# Order339499-SandyNoble-Polarshield_v1_4a.net
KiCad netlist of a schematic drawn in EAGLE
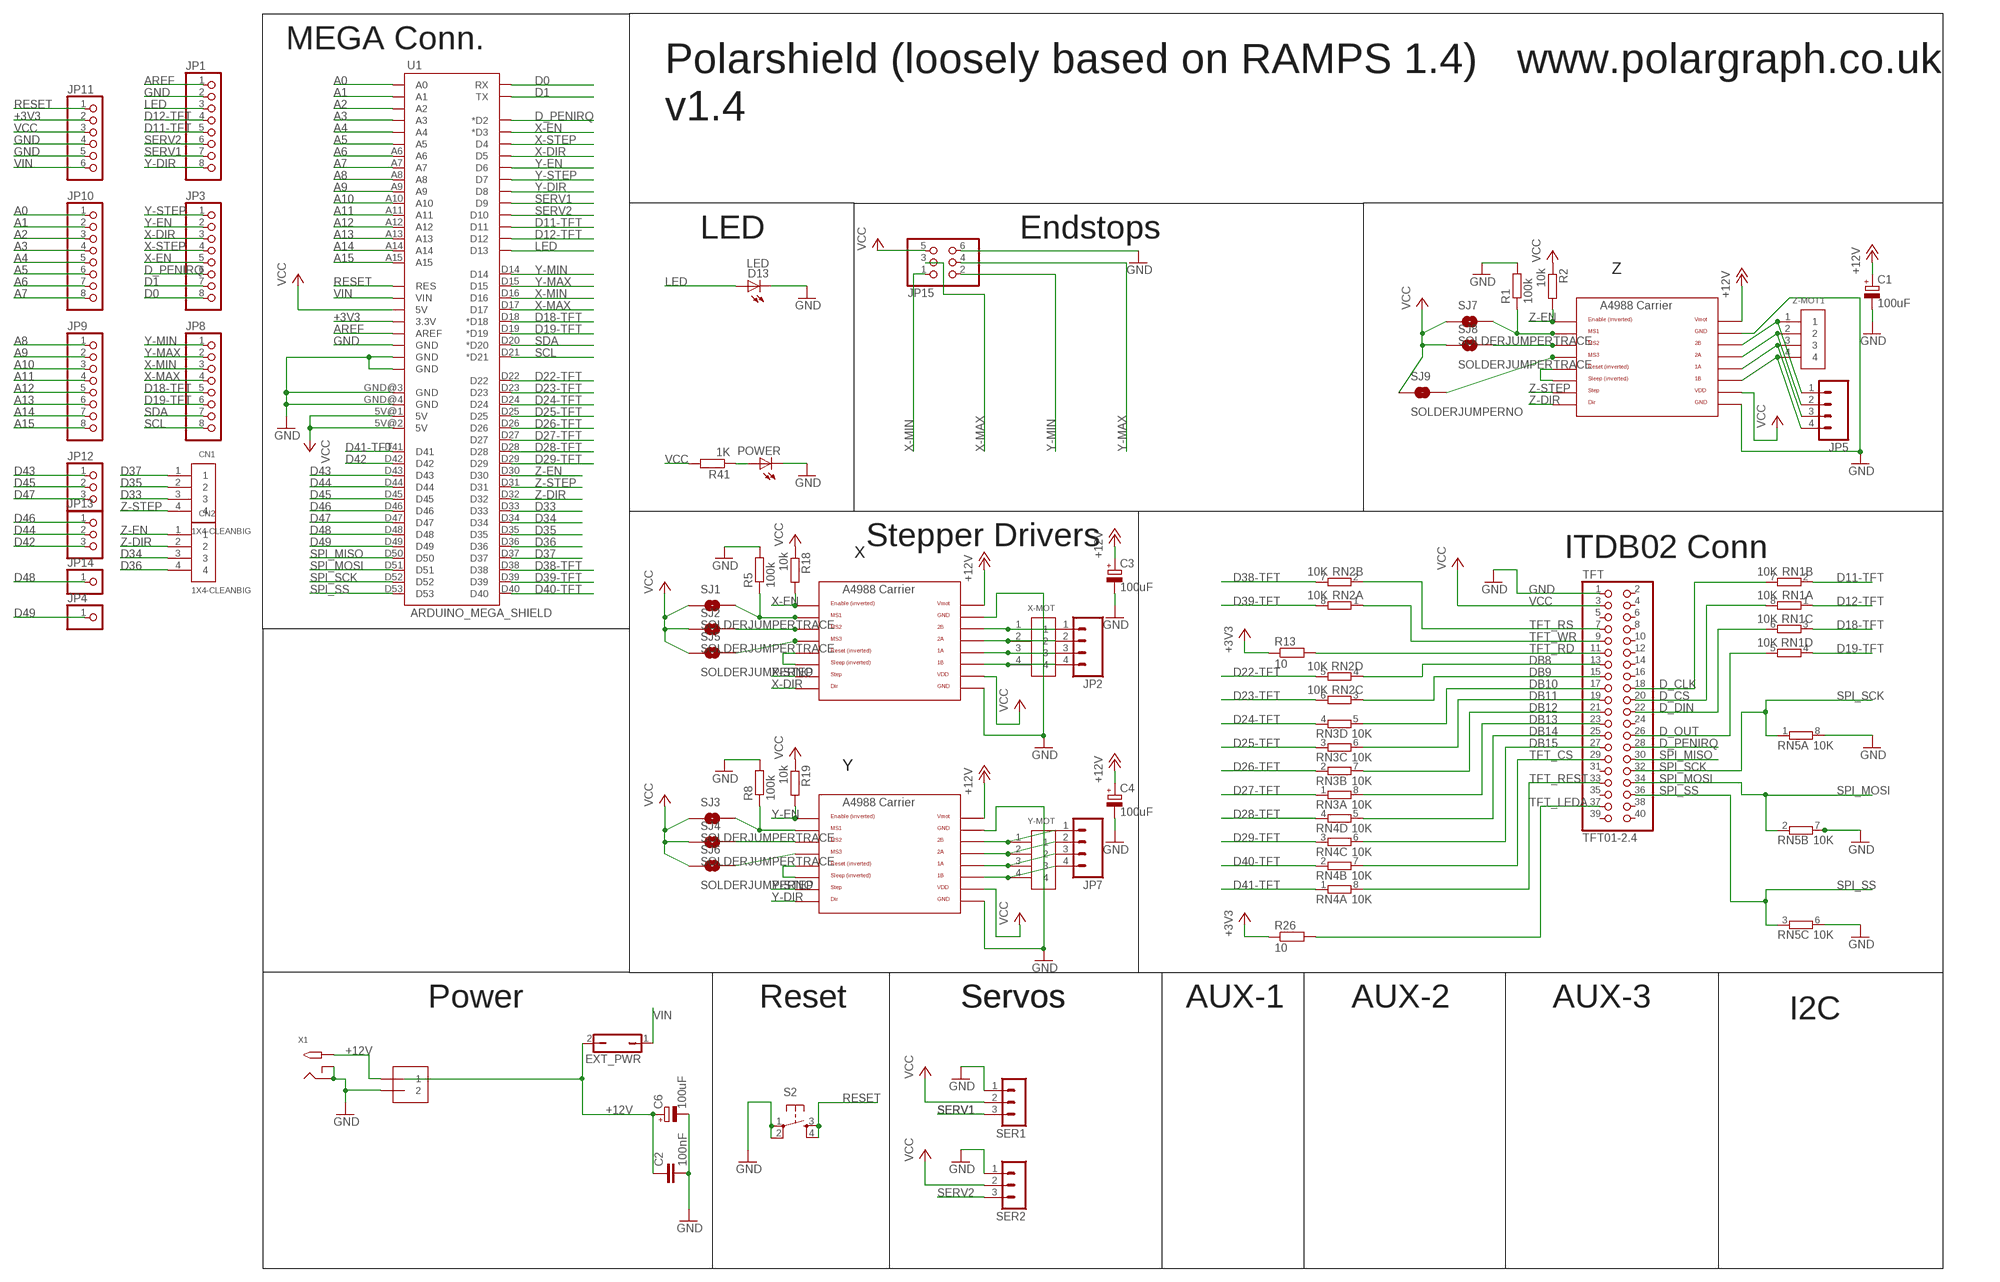
[diagram p0: schematic, sheet 1]

(export (version "E")
  (design (tool "Eeschema 10.0.6"))
  (components
    (comp (ref "C1")
      (value "100uF")
      (footprint "eagle-import:153CLV-0605")
      (libsource (lib "eagle-import") (part "CPOL-EU153CLV-0605"))
    )
    (comp (ref "C2")
      (value "100nF")
      (footprint "eagle-import:C0805")
      (libsource (lib "eagle-import") (part "C-EUC0805"))
    )
    (comp (ref "C3")
      (value "100uF")
      (footprint "eagle-import:153CLV-0605")
      (libsource (lib "eagle-import") (part "CPOL-EU153CLV-0605"))
    )
    (comp (ref "C4")
      (value "100uF")
      (footprint "eagle-import:153CLV-0605")
      (libsource (lib "eagle-import") (part "CPOL-EU153CLV-0605"))
    )
    (comp (ref "C6")
      (value "100uF")
      (footprint "eagle-import:153CLV-0605")
      (libsource (lib "eagle-import") (part "CPOL-EU153CLV-0605"))
    )
    (comp (ref "CN1")
      (value "1X4-CLEANBIG")
      (footprint "eagle-import:1X04-CLEANBIG")
      (libsource (lib "eagle-import") (part "1X4-CLEANBIG"))
    )
    (comp (ref "CN2")
      (value "1X4-CLEANBIG")
      (footprint "eagle-import:1X04-CLEANBIG")
      (libsource (lib "eagle-import") (part "1X4-CLEANBIG"))
    )
    (comp (ref "D13")
      (value "LED")
      (footprint "eagle-import:CHIP-LED0805")
      (libsource (lib "eagle-import") (part "LEDCHIP-LED0805"))
    )
    (comp (ref "EXT_PWR")
      (value "JP1Q")
      (footprint "eagle-import:JP1")
      (libsource (lib "eagle-import") (part "JP1Q"))
    )
    (comp (ref "J1")
      (value "1X2-3.5MM")
      (footprint "eagle-import:1X2-3.5MM")
      (libsource (lib "eagle-import") (part "1X2-3.5MM"))
    )
    (comp (ref "JP1")
      (value "PINHD-1X8CLEANBIG")
      (footprint "eagle-import:1X08-CLEANBIG")
      (libsource (lib "eagle-import") (part "PINHD-1X8CLEANBIG"))
    )
    (comp (ref "JP2")
      (value "M04SCREW")
      (footprint "eagle-import:SCREWTERMINAL-3.5MM-4")
      (libsource (lib "eagle-import") (part "M04SCREW"))
    )
    (comp (ref "JP3")
      (value "PINHD-1X8CLEANBIG")
      (footprint "eagle-import:1X08-CLEANBIG")
      (libsource (lib "eagle-import") (part "PINHD-1X8CLEANBIG"))
    )
    (comp (ref "JP4")
      (value "PINHD-1X1CB")
      (footprint "eagle-import:1X01-CLEANBIG")
      (libsource (lib "eagle-import") (part "PINHD-1X1CB"))
    )
    (comp (ref "JP5")
      (value "M04SCREW")
      (footprint "eagle-import:SCREWTERMINAL-3.5MM-4")
      (libsource (lib "eagle-import") (part "M04SCREW"))
    )
    (comp (ref "JP7")
      (value "M04SCREW")
      (footprint "eagle-import:SCREWTERMINAL-3.5MM-4")
      (libsource (lib "eagle-import") (part "M04SCREW"))
    )
    (comp (ref "JP8")
      (value "PINHD-1X8CLEANBIG")
      (footprint "eagle-import:1X08-CLEANBIG")
      (libsource (lib "eagle-import") (part "PINHD-1X8CLEANBIG"))
    )
    (comp (ref "JP9")
      (value "PINHD-1X8CLEANBIG")
      (footprint "eagle-import:1X08-CLEANBIG")
      (libsource (lib "eagle-import") (part "PINHD-1X8CLEANBIG"))
    )
    (comp (ref "JP10")
      (value "PINHD-1X8CLEANBIG")
      (footprint "eagle-import:1X08-CLEANBIG")
      (libsource (lib "eagle-import") (part "PINHD-1X8CLEANBIG"))
    )
    (comp (ref "JP11")
      (value "PINHD-1X6CB")
      (footprint "eagle-import:1X06-CLEANBIG")
      (libsource (lib "eagle-import") (part "PINHD-1X6CB"))
    )
    (comp (ref "JP12")
      (value "PINHD-1X3CB")
      (footprint "eagle-import:1X03-CLEANBIG")
      (libsource (lib "eagle-import") (part "PINHD-1X3CB"))
    )
    (comp (ref "JP13")
      (value "PINHD-1X3CB")
      (footprint "eagle-import:1X03-CLEANBIG")
      (libsource (lib "eagle-import") (part "PINHD-1X3CB"))
    )
    (comp (ref "JP14")
      (value "PINHD-1X1CB")
      (footprint "eagle-import:1X01-CLEANBIG")
      (libsource (lib "eagle-import") (part "PINHD-1X1CB"))
    )
    (comp (ref "JP15")
      (value "PINHD-2X3")
      (footprint "eagle-import:2X03")
      (libsource (lib "eagle-import") (part "PINHD-2X3"))
    )
    (comp (ref "POWER")
      (value "LEDCHIP-LED0805")
      (footprint "eagle-import:CHIP-LED0805")
      (libsource (lib "eagle-import") (part "LEDCHIP-LED0805"))
    )
    (comp (ref "R1")
      (value "100k")
      (footprint "eagle-import:R0805")
      (libsource (lib "eagle-import") (part "R-EU_R0805"))
    )
    (comp (ref "R2")
      (value "10k")
      (footprint "eagle-import:R0805")
      (libsource (lib "eagle-import") (part "R-EU_R0805"))
    )
    (comp (ref "R5")
      (value "100k")
      (footprint "eagle-import:R0805")
      (libsource (lib "eagle-import") (part "R-EU_R0805"))
    )
    (comp (ref "R8")
      (value "100k")
      (footprint "eagle-import:R0805")
      (libsource (lib "eagle-import") (part "R-EU_R0805"))
    )
    (comp (ref "R13")
      (value "10")
      (footprint "eagle-import:R0805")
      (libsource (lib "eagle-import") (part "resistor_R-EU_R0805"))
    )
    (comp (ref "R18")
      (value "10k")
      (footprint "eagle-import:R0805")
      (libsource (lib "eagle-import") (part "R-EU_R0805"))
    )
    (comp (ref "R19")
      (value "10k")
      (footprint "eagle-import:R0805")
      (libsource (lib "eagle-import") (part "R-EU_R0805"))
    )
    (comp (ref "R26")
      (value "10")
      (footprint "eagle-import:R0805")
      (libsource (lib "eagle-import") (part "resistor_R-EU_R0805"))
    )
    (comp (ref "R41")
      (value "1K")
      (footprint "eagle-import:R0805")
      (libsource (lib "eagle-import") (part "R-EU_R0805"))
    )
    (comp (ref "RN1")
      (value "10K")
      (footprint "eagle-import:EXBS8V")
      (libsource (lib "eagle-import") (part "4R-NEXBS8V"))
    )
    (comp (ref "RN2")
      (value "10K")
      (footprint "eagle-import:EXBS8V")
      (libsource (lib "eagle-import") (part "4R-NEXBS8V"))
    )
    (comp (ref "RN3")
      (value "10K")
      (footprint "eagle-import:EXBS8V")
      (libsource (lib "eagle-import") (part "4R-NEXBS8V"))
    )
    (comp (ref "RN4")
      (value "10K")
      (footprint "eagle-import:EXBS8V")
      (libsource (lib "eagle-import") (part "4R-NEXBS8V"))
    )
    (comp (ref "RN5")
      (value "10K")
      (footprint "eagle-import:EXBS8V")
      (libsource (lib "eagle-import") (part "4R-NEXBS8V"))
    )
    (comp (ref "S2")
      (value "TAC_SWITCHPTH")
      (footprint "eagle-import:TACTILE-PTH")
      (libsource (lib "eagle-import") (part "TAC_SWITCHPTH"))
    )
    (comp (ref "SER1")
      (value "3PIN-HEADER")
      (footprint "eagle-import:3PIN-HEADER")
      (libsource (lib "eagle-import") (part "3PIN-HEADER"))
    )
    (comp (ref "SER2")
      (value "3PIN-HEADER")
      (footprint "eagle-import:3PIN-HEADER")
      (libsource (lib "eagle-import") (part "3PIN-HEADER"))
    )
    (comp (ref "SJ1")
      (value "SOLDERJUMPERTRACE")
      (footprint "eagle-import:SJ_2S-TRACE")
      (libsource (lib "eagle-import") (part "SOLDERJUMPERTRACE"))
    )
    (comp (ref "SJ2")
      (value "SOLDERJUMPERTRACE")
      (footprint "eagle-import:SJ_2S-TRACE")
      (libsource (lib "eagle-import") (part "SOLDERJUMPERTRACE"))
    )
    (comp (ref "SJ3")
      (value "SOLDERJUMPERTRACE")
      (footprint "eagle-import:SJ_2S-TRACE")
      (libsource (lib "eagle-import") (part "SOLDERJUMPERTRACE"))
    )
    (comp (ref "SJ4")
      (value "SOLDERJUMPERTRACE")
      (footprint "eagle-import:SJ_2S-TRACE")
      (libsource (lib "eagle-import") (part "SOLDERJUMPERTRACE"))
    )
    (comp (ref "SJ5")
      (value "SOLDERJUMPERNO")
      (footprint "eagle-import:SJ_2S-NO")
      (libsource (lib "eagle-import") (part "SOLDERJUMPERNO"))
    )
    (comp (ref "SJ6")
      (value "SOLDERJUMPERNO")
      (footprint "eagle-import:SJ_2S-NO")
      (libsource (lib "eagle-import") (part "SOLDERJUMPERNO"))
    )
    (comp (ref "SJ7")
      (value "SOLDERJUMPERTRACE")
      (footprint "eagle-import:SJ_2S-TRACE")
      (libsource (lib "eagle-import") (part "SOLDERJUMPERTRACE"))
    )
    (comp (ref "SJ8")
      (value "SOLDERJUMPERTRACE")
      (footprint "eagle-import:SJ_2S-TRACE")
      (libsource (lib "eagle-import") (part "SOLDERJUMPERTRACE"))
    )
    (comp (ref "SJ9")
      (value "SOLDERJUMPERNO")
      (footprint "eagle-import:SJ_2S-NO")
      (libsource (lib "eagle-import") (part "SOLDERJUMPERNO"))
    )
    (comp (ref "TFT")
      (value "TFT01-2.4")
      (footprint "eagle-import:TFT01-2.4")
      (libsource (lib "eagle-import") (part "TFT01-2.4"))
    )
    (comp (ref "U$1")
      (value "A4988BREAKOUT")
      (footprint "eagle-import:A4988BREAKOUT")
      (libsource (lib "eagle-import") (part "A4988BREAKOUT"))
    )
    (comp (ref "U$6")
      (value "A4988BREAKOUT")
      (footprint "eagle-import:A4988BREAKOUT")
      (libsource (lib "eagle-import") (part "A4988BREAKOUT"))
    )
    (comp (ref "U$7")
      (value "A4988BREAKOUT")
      (footprint "eagle-import:A4988BREAKOUT")
      (libsource (lib "eagle-import") (part "A4988BREAKOUT"))
    )
    (comp (ref "U1")
      (value "ARDUINO_MEGA_SHIELD")
      (footprint "eagle-import:ARDUINO_MEGA_SHIELD")
      (libsource (lib "eagle-import") (part "ARDUINO_MEGA_SHIELD"))
    )
    (comp (ref "X-MOT")
      (value "1X4-BIG")
      (footprint "eagle-import:1X04-BIG")
      (libsource (lib "eagle-import") (part "1X4-BIG"))
    )
    (comp (ref "X1")
      (value "2.1MMJACKTHM")
      (footprint "eagle-import:PJ-102A")
      (libsource (lib "eagle-import") (part "2.1MMJACKTHM"))
    )
    (comp (ref "Y-MOT")
      (value "1X4-BIG")
      (footprint "eagle-import:1X04-BIG")
      (libsource (lib "eagle-import") (part "1X4-BIG"))
    )
    (comp (ref "Z-MOT1")
      (value "1X4-BIG")
      (footprint "eagle-import:1X04-BIG")
      (libsource (lib "eagle-import") (part "1X4-BIG"))
    )
  )
  (nets
    (net (code "1") (name "+3V3") (class "Default")
      (node (ref "JP11") (pin "2") (pinfunction "2_2") (pintype "passive"))
      (node (ref "R13") (pin "1") (pinfunction "1_1") (pintype "passive"))
      (node (ref "R26") (pin "1") (pinfunction "1_1") (pintype "passive"))
      (node (ref "U1") (pin "3.3V") (pinfunction "3.3V_3.3V") (pintype "bidirectional"))
    )
    (net (code "2") (name "+12V") (class "Default")
      (node (ref "C1") (pin "+") (pinfunction "+_+") (pintype "passive"))
      (node (ref "C2") (pin "1") (pinfunction "1_1") (pintype "passive"))
      (node (ref "C3") (pin "+") (pinfunction "+_+") (pintype "passive"))
      (node (ref "C4") (pin "+") (pinfunction "+_+") (pintype "passive"))
      (node (ref "C6") (pin "+") (pinfunction "+_+") (pintype "passive"))
      (node (ref "EXT_PWR") (pin "2") (pinfunction "2_2") (pintype "passive"))
      (node (ref "J1") (pin "1") (pinfunction "1_1") (pintype "passive"))
      (node (ref "U$1") (pin "VMOT") (pinfunction "VMOT_VMOT") (pintype "power_in"))
      (node (ref "U$6") (pin "VMOT") (pinfunction "VMOT_VMOT") (pintype "power_in"))
      (node (ref "U$7") (pin "VMOT") (pinfunction "VMOT_VMOT") (pintype "power_in"))
      (node (ref "X1") (pin "TIP") (pinfunction "TIP_TIP") (pintype "bidirectional"))
    )
    (net (code "3") (name "/A0") (class "Default")
      (node (ref "JP10") (pin "1") (pinfunction "1_1") (pintype "passive"))
      (node (ref "U1") (pin "A0") (pinfunction "A0_A0") (pintype "bidirectional"))
    )
    (net (code "4") (name "/A1") (class "Default")
      (node (ref "JP10") (pin "2") (pinfunction "2_2") (pintype "passive"))
      (node (ref "U1") (pin "A1") (pinfunction "A1_A1") (pintype "bidirectional"))
    )
    (net (code "5") (name "/A2") (class "Default")
      (node (ref "JP10") (pin "3") (pinfunction "3_3") (pintype "passive"))
      (node (ref "U1") (pin "A2") (pinfunction "A2_A2") (pintype "bidirectional"))
    )
    (net (code "6") (name "/A3") (class "Default")
      (node (ref "JP10") (pin "4") (pinfunction "4_4") (pintype "passive"))
      (node (ref "U1") (pin "A3") (pinfunction "A3_A3") (pintype "bidirectional"))
    )
    (net (code "7") (name "/A4") (class "Default")
      (node (ref "JP10") (pin "5") (pinfunction "5_5") (pintype "passive"))
      (node (ref "U1") (pin "A4") (pinfunction "A4_A4") (pintype "bidirectional"))
    )
    (net (code "8") (name "/A5") (class "Default")
      (node (ref "JP10") (pin "6") (pinfunction "6_6") (pintype "passive"))
      (node (ref "U1") (pin "A5") (pinfunction "A5_A5") (pintype "bidirectional"))
    )
    (net (code "9") (name "/A6") (class "Default")
      (node (ref "JP10") (pin "7") (pinfunction "7_7") (pintype "passive"))
      (node (ref "U1") (pin "A6") (pinfunction "A6_A6") (pintype "bidirectional"))
    )
    (net (code "10") (name "/A7") (class "Default")
      (node (ref "JP10") (pin "8") (pinfunction "8_8") (pintype "passive"))
      (node (ref "U1") (pin "A7") (pinfunction "A7_A7") (pintype "bidirectional"))
    )
    (net (code "11") (name "/A8") (class "Default")
      (node (ref "JP9") (pin "1") (pinfunction "1_1") (pintype "passive"))
      (node (ref "U1") (pin "A8") (pinfunction "A8_A8") (pintype "bidirectional"))
    )
    (net (code "12") (name "/A9") (class "Default")
      (node (ref "JP9") (pin "2") (pinfunction "2_2") (pintype "passive"))
      (node (ref "U1") (pin "A9") (pinfunction "A9_A9") (pintype "bidirectional"))
    )
    (net (code "13") (name "/A10") (class "Default")
      (node (ref "JP9") (pin "3") (pinfunction "3_3") (pintype "passive"))
      (node (ref "U1") (pin "A10") (pinfunction "A10_A10") (pintype "bidirectional"))
    )
    (net (code "14") (name "/A11") (class "Default")
      (node (ref "JP9") (pin "4") (pinfunction "4_4") (pintype "passive"))
      (node (ref "U1") (pin "A11") (pinfunction "A11_A11") (pintype "bidirectional"))
    )
    (net (code "15") (name "/A12") (class "Default")
      (node (ref "JP9") (pin "5") (pinfunction "5_5") (pintype "passive"))
      (node (ref "U1") (pin "A12") (pinfunction "A12_A12") (pintype "bidirectional"))
    )
    (net (code "16") (name "/A13") (class "Default")
      (node (ref "JP9") (pin "6") (pinfunction "6_6") (pintype "passive"))
      (node (ref "U1") (pin "A13") (pinfunction "A13_A13") (pintype "bidirectional"))
    )
    (net (code "17") (name "/A14") (class "Default")
      (node (ref "JP9") (pin "7") (pinfunction "7_7") (pintype "passive"))
      (node (ref "U1") (pin "A14") (pinfunction "A14_A14") (pintype "bidirectional"))
    )
    (net (code "18") (name "/A15") (class "Default")
      (node (ref "JP9") (pin "8") (pinfunction "8_8") (pintype "passive"))
      (node (ref "U1") (pin "A15") (pinfunction "A15_A15") (pintype "bidirectional"))
    )
    (net (code "19") (name "/AREF") (class "Default")
      (node (ref "JP1") (pin "1") (pinfunction "1_1") (pintype "passive"))
      (node (ref "U1") (pin "AREF") (pinfunction "AREF_AREF") (pintype "bidirectional"))
    )
    (net (code "20") (name "/D0") (class "Default")
      (node (ref "JP3") (pin "8") (pinfunction "8_8") (pintype "passive"))
      (node (ref "U1") (pin "RX") (pinfunction "RX_RX") (pintype "bidirectional"))
    )
    (net (code "21") (name "/D1") (class "Default")
      (node (ref "JP3") (pin "7") (pinfunction "7_7") (pintype "passive"))
      (node (ref "U1") (pin "TX") (pinfunction "TX_TX") (pintype "bidirectional"))
    )
    (net (code "22") (name "/D11-TFT") (class "Default")
      (node (ref "JP1") (pin "5") (pinfunction "5_5") (pintype "passive"))
      (node (ref "RN1") (pin "2") (pinfunction "1_2") (pintype "passive"))
      (node (ref "U1") (pin "D11") (pinfunction "D11_D11") (pintype "bidirectional"))
    )
    (net (code "23") (name "/D12-TFT") (class "Default")
      (node (ref "JP1") (pin "4") (pinfunction "4_4") (pintype "passive"))
      (node (ref "RN1") (pin "1") (pinfunction "1_1") (pintype "passive"))
      (node (ref "U1") (pin "D12") (pinfunction "D12_D12") (pintype "bidirectional"))
    )
    (net (code "24") (name "/D18-TFT") (class "Default")
      (node (ref "JP8") (pin "5") (pinfunction "5_5") (pintype "passive"))
      (node (ref "RN1") (pin "3") (pinfunction "1_3") (pintype "passive"))
      (node (ref "U1") (pin "D18") (pinfunction "*D18_D18") (pintype "bidirectional"))
    )
    (net (code "25") (name "/D19-TFT") (class "Default")
      (node (ref "JP8") (pin "6") (pinfunction "6_6") (pintype "passive"))
      (node (ref "RN1") (pin "4") (pinfunction "1_4") (pintype "passive"))
      (node (ref "U1") (pin "D19") (pinfunction "*D19_D19") (pintype "bidirectional"))
    )
    (net (code "26") (name "/D22-TFT") (class "Default")
      (node (ref "RN2") (pin "5") (pinfunction "2_5") (pintype "passive"))
      (node (ref "U1") (pin "D22") (pinfunction "D22_D22") (pintype "bidirectional"))
    )
    (net (code "27") (name "/D23-TFT") (class "Default")
      (node (ref "RN2") (pin "6") (pinfunction "2_6") (pintype "passive"))
      (node (ref "U1") (pin "D23") (pinfunction "D23_D23") (pintype "bidirectional"))
    )
    (net (code "28") (name "/D24-TFT") (class "Default")
      (node (ref "RN3") (pin "4") (pinfunction "1_4") (pintype "passive"))
      (node (ref "U1") (pin "D24") (pinfunction "D24_D24") (pintype "bidirectional"))
    )
    (net (code "29") (name "/D25-TFT") (class "Default")
      (node (ref "RN3") (pin "3") (pinfunction "1_3") (pintype "passive"))
      (node (ref "U1") (pin "D25") (pinfunction "D25_D25") (pintype "bidirectional"))
    )
    (net (code "30") (name "/D26-TFT") (class "Default")
      (node (ref "RN3") (pin "2") (pinfunction "1_2") (pintype "passive"))
      (node (ref "U1") (pin "D26") (pinfunction "D26_D26") (pintype "bidirectional"))
    )
    (net (code "31") (name "/D27-TFT") (class "Default")
      (node (ref "RN3") (pin "1") (pinfunction "1_1") (pintype "passive"))
      (node (ref "U1") (pin "D27") (pinfunction "D27_D27") (pintype "bidirectional"))
    )
    (net (code "32") (name "/D28-TFT") (class "Default")
      (node (ref "RN4") (pin "4") (pinfunction "1_4") (pintype "passive"))
      (node (ref "U1") (pin "D28") (pinfunction "D28_D28") (pintype "bidirectional"))
    )
    (net (code "33") (name "/D29-TFT") (class "Default")
      (node (ref "RN4") (pin "3") (pinfunction "1_3") (pintype "passive"))
      (node (ref "U1") (pin "D29") (pinfunction "D29_D29") (pintype "bidirectional"))
    )
    (net (code "34") (name "/D33") (class "Default")
      (node (ref "CN1") (pin "3") (pinfunction "3_3") (pintype "bidirectional"))
      (node (ref "U1") (pin "D33") (pinfunction "D33_D33") (pintype "bidirectional"))
    )
    (net (code "35") (name "/D34") (class "Default")
      (node (ref "CN2") (pin "3") (pinfunction "3_3") (pintype "bidirectional"))
      (node (ref "U1") (pin "D34") (pinfunction "D34_D34") (pintype "bidirectional"))
    )
    (net (code "36") (name "/D35") (class "Default")
      (node (ref "CN1") (pin "2") (pinfunction "2_2") (pintype "bidirectional"))
      (node (ref "U1") (pin "D35") (pinfunction "D35_D35") (pintype "bidirectional"))
    )
    (net (code "37") (name "/D36") (class "Default")
      (node (ref "CN2") (pin "4") (pinfunction "4_4") (pintype "bidirectional"))
      (node (ref "U1") (pin "D36") (pinfunction "D36_D36") (pintype "bidirectional"))
    )
    (net (code "38") (name "/D37") (class "Default")
      (node (ref "CN1") (pin "1") (pinfunction "1_1") (pintype "bidirectional"))
      (node (ref "U1") (pin "D37") (pinfunction "D37_D37") (pintype "bidirectional"))
    )
    (net (code "39") (name "/D38-TFT") (class "Default")
      (node (ref "RN2") (pin "7") (pinfunction "2_7") (pintype "passive"))
      (node (ref "U1") (pin "D38") (pinfunction "D38_D38") (pintype "bidirectional"))
    )
    (net (code "40") (name "/D39-TFT") (class "Default")
      (node (ref "RN2") (pin "8") (pinfunction "2_8") (pintype "passive"))
      (node (ref "U1") (pin "D39") (pinfunction "D39_D39") (pintype "bidirectional"))
    )
    (net (code "41") (name "/D40-TFT") (class "Default")
      (node (ref "RN4") (pin "2") (pinfunction "1_2") (pintype "passive"))
      (node (ref "U1") (pin "D40") (pinfunction "D40_D40") (pintype "bidirectional"))
    )
    (net (code "42") (name "/D41-TFT") (class "Default")
      (node (ref "RN4") (pin "1") (pinfunction "1_1") (pintype "passive"))
      (node (ref "U1") (pin "D41") (pinfunction "D41_D41") (pintype "bidirectional"))
    )
    (net (code "43") (name "/D42") (class "Default")
      (node (ref "JP13") (pin "3") (pinfunction "3_3") (pintype "passive"))
      (node (ref "U1") (pin "D42") (pinfunction "D42_D42") (pintype "bidirectional"))
    )
    (net (code "44") (name "/D43") (class "Default")
      (node (ref "JP12") (pin "1") (pinfunction "1_1") (pintype "passive"))
      (node (ref "U1") (pin "D43") (pinfunction "D43_D43") (pintype "bidirectional"))
    )
    (net (code "45") (name "/D44") (class "Default")
      (node (ref "JP13") (pin "2") (pinfunction "2_2") (pintype "passive"))
      (node (ref "U1") (pin "D44") (pinfunction "D44_D44") (pintype "bidirectional"))
    )
    (net (code "46") (name "/D45") (class "Default")
      (node (ref "JP12") (pin "2") (pinfunction "2_2") (pintype "passive"))
      (node (ref "U1") (pin "D45") (pinfunction "D45_D45") (pintype "bidirectional"))
    )
    (net (code "47") (name "/D46") (class "Default")
      (node (ref "JP13") (pin "1") (pinfunction "1_1") (pintype "passive"))
      (node (ref "U1") (pin "D46") (pinfunction "D46_D46") (pintype "bidirectional"))
    )
    (net (code "48") (name "/D47") (class "Default")
      (node (ref "JP12") (pin "3") (pinfunction "3_3") (pintype "passive"))
      (node (ref "U1") (pin "D47") (pinfunction "D47_D47") (pintype "bidirectional"))
    )
    (net (code "49") (name "/D48") (class "Default")
      (node (ref "JP14") (pin "1") (pinfunction "1_1") (pintype "passive"))
      (node (ref "U1") (pin "D48") (pinfunction "D48_D48") (pintype "bidirectional"))
    )
    (net (code "50") (name "/D49") (class "Default")
      (node (ref "JP4") (pin "1") (pinfunction "1_1") (pintype "passive"))
      (node (ref "U1") (pin "D49") (pinfunction "D49_D49") (pintype "bidirectional"))
    )
    (net (code "51") (name "/DB8") (class "Default")
      (node (ref "RN2") (pin "4") (pinfunction "1_4") (pintype "passive"))
      (node (ref "TFT") (pin "13") (pinfunction "13_13") (pintype "passive"))
    )
    (net (code "52") (name "/DB9") (class "Default")
      (node (ref "RN2") (pin "3") (pinfunction "1_3") (pintype "passive"))
      (node (ref "TFT") (pin "15") (pinfunction "15_15") (pintype "passive"))
    )
    (net (code "53") (name "/DB10") (class "Default")
      (node (ref "RN3") (pin "5") (pinfunction "2_5") (pintype "passive"))
      (node (ref "TFT") (pin "17") (pinfunction "17_17") (pintype "passive"))
    )
    (net (code "54") (name "/DB11") (class "Default")
      (node (ref "RN3") (pin "6") (pinfunction "2_6") (pintype "passive"))
      (node (ref "TFT") (pin "19") (pinfunction "19_19") (pintype "passive"))
    )
    (net (code "55") (name "/DB12") (class "Default")
      (node (ref "RN3") (pin "7") (pinfunction "2_7") (pintype "passive"))
      (node (ref "TFT") (pin "21") (pinfunction "21_21") (pintype "passive"))
    )
    (net (code "56") (name "/DB13") (class "Default")
      (node (ref "RN3") (pin "8") (pinfunction "2_8") (pintype "passive"))
      (node (ref "TFT") (pin "23") (pinfunction "23_23") (pintype "passive"))
    )
    (net (code "57") (name "/DB14") (class "Default")
      (node (ref "RN4") (pin "5") (pinfunction "2_5") (pintype "passive"))
      (node (ref "TFT") (pin "25") (pinfunction "25_25") (pintype "passive"))
    )
    (net (code "58") (name "/DB15") (class "Default")
      (node (ref "RN4") (pin "6") (pinfunction "2_6") (pintype "passive"))
      (node (ref "TFT") (pin "27") (pinfunction "27_27") (pintype "passive"))
    )
    (net (code "59") (name "/D_CLK") (class "Default")
      (node (ref "RN1") (pin "7") (pinfunction "2_7") (pintype "passive"))
      (node (ref "TFT") (pin "18") (pinfunction "18_18") (pintype "passive"))
    )
    (net (code "60") (name "/D_CS") (class "Default")
      (node (ref "RN1") (pin "8") (pinfunction "2_8") (pintype "passive"))
      (node (ref "TFT") (pin "20") (pinfunction "20_20") (pintype "passive"))
    )
    (net (code "61") (name "/D_DIN") (class "Default")
      (node (ref "RN1") (pin "6") (pinfunction "2_6") (pintype "passive"))
      (node (ref "TFT") (pin "22") (pinfunction "22_22") (pintype "passive"))
    )
    (net (code "62") (name "/D_OUT") (class "Default")
      (node (ref "RN1") (pin "5") (pinfunction "2_5") (pintype "passive"))
      (node (ref "TFT") (pin "26") (pinfunction "26_26") (pintype "passive"))
    )
    (net (code "63") (name "/D_PENIRQ") (class "Default")
      (node (ref "JP3") (pin "6") (pinfunction "6_6") (pintype "passive"))
      (node (ref "TFT") (pin "28") (pinfunction "28_28") (pintype "passive"))
      (node (ref "U1") (pin "D2") (pinfunction "*D2_D2") (pintype "bidirectional"))
    )
    (net (code "64") (name "/LED") (class "Default")
      (node (ref "D13") (pin "A") (pinfunction "A_A") (pintype "passive"))
      (node (ref "JP1") (pin "3") (pinfunction "3_3") (pintype "passive"))
      (node (ref "U1") (pin "D13") (pinfunction "D13_D13") (pintype "bidirectional"))
    )
    (net (code "65") (name "/RESET") (class "Default")
      (node (ref "JP11") (pin "1") (pinfunction "1_1") (pintype "passive"))
      (node (ref "S2") (pin "3") (pinfunction "3_3") (pintype "passive"))
      (node (ref "S2") (pin "4") (pinfunction "4_4") (pintype "passive"))
      (node (ref "U1") (pin "RES") (pinfunction "RES_RES") (pintype "bidirectional"))
    )
    (net (code "66") (name "/SCL") (class "Default")
      (node (ref "JP8") (pin "8") (pinfunction "8_8") (pintype "passive"))
      (node (ref "U1") (pin "D21") (pinfunction "*D21_D21") (pintype "bidirectional"))
    )
    (net (code "67") (name "/SDA") (class "Default")
      (node (ref "JP8") (pin "7") (pinfunction "7_7") (pintype "passive"))
      (node (ref "U1") (pin "D20") (pinfunction "*D20_D20") (pintype "bidirectional"))
    )
    (net (code "68") (name "/SERV1") (class "Default")
      (node (ref "JP1") (pin "7") (pinfunction "7_7") (pintype "passive"))
      (node (ref "SER1") (pin "3") (pinfunction "3_3") (pintype "passive"))
      (node (ref "U1") (pin "D9") (pinfunction "D9_D9") (pintype "bidirectional"))
    )
    (net (code "69") (name "/SERV2") (class "Default")
      (node (ref "JP1") (pin "6") (pinfunction "6_6") (pintype "passive"))
      (node (ref "SER2") (pin "3") (pinfunction "3_3") (pintype "passive"))
      (node (ref "U1") (pin "D10") (pinfunction "D10_D10") (pintype "bidirectional"))
    )
    (net (code "70") (name "/SPI_MISO") (class "Default")
      (node (ref "TFT") (pin "30") (pinfunction "30_30") (pintype "passive"))
      (node (ref "U1") (pin "D50") (pinfunction "D50_D50") (pintype "bidirectional"))
    )
    (net (code "71") (name "/SPI_MOSI") (class "Default")
      (node (ref "RN5") (pin "2") (pinfunction "1_2") (pintype "passive"))
      (node (ref "TFT") (pin "34") (pinfunction "34_34") (pintype "passive"))
      (node (ref "U1") (pin "D51") (pinfunction "D51_D51") (pintype "bidirectional"))
    )
    (net (code "72") (name "/SPI_SCK") (class "Default")
      (node (ref "RN5") (pin "1") (pinfunction "1_1") (pintype "passive"))
      (node (ref "TFT") (pin "32") (pinfunction "32_32") (pintype "passive"))
      (node (ref "U1") (pin "D52") (pinfunction "D52_D52") (pintype "bidirectional"))
    )
    (net (code "73") (name "/SPI_SS") (class "Default")
      (node (ref "RN5") (pin "3") (pinfunction "1_3") (pintype "passive"))
      (node (ref "TFT") (pin "36") (pinfunction "36_36") (pintype "passive"))
      (node (ref "U1") (pin "D53") (pinfunction "D53_D53") (pintype "bidirectional"))
    )
    (net (code "74") (name "/TFT_CS") (class "Default")
      (node (ref "RN4") (pin "7") (pinfunction "2_7") (pintype "passive"))
      (node (ref "TFT") (pin "29") (pinfunction "29_29") (pintype "passive"))
    )
    (net (code "75") (name "/TFT_LEDA") (class "Default")
      (node (ref "R26") (pin "2") (pinfunction "2_2") (pintype "passive"))
      (node (ref "TFT") (pin "37") (pinfunction "37_37") (pintype "passive"))
    )
    (net (code "76") (name "/TFT_RD") (class "Default")
      (node (ref "R13") (pin "2") (pinfunction "2_2") (pintype "passive"))
      (node (ref "TFT") (pin "11") (pinfunction "11_11") (pintype "passive"))
    )
    (net (code "77") (name "/TFT_REST") (class "Default")
      (node (ref "RN4") (pin "8") (pinfunction "2_8") (pintype "passive"))
      (node (ref "TFT") (pin "33") (pinfunction "33_33") (pintype "passive"))
    )
    (net (code "78") (name "/TFT_RS") (class "Default")
      (node (ref "RN2") (pin "2") (pinfunction "1_2") (pintype "passive"))
      (node (ref "TFT") (pin "7") (pinfunction "7_7") (pintype "passive"))
    )
    (net (code "79") (name "/TFT_WR") (class "Default")
      (node (ref "RN2") (pin "1") (pinfunction "1_1") (pintype "passive"))
      (node (ref "TFT") (pin "9") (pinfunction "9_9") (pintype "passive"))
    )
    (net (code "80") (name "/VIN") (class "Default")
      (node (ref "EXT_PWR") (pin "1") (pinfunction "1_1") (pintype "passive"))
      (node (ref "JP11") (pin "6") (pinfunction "6_6") (pintype "passive"))
      (node (ref "U1") (pin "VIN") (pinfunction "VIN_VIN") (pintype "bidirectional"))
    )
    (net (code "81") (name "/X-DIR") (class "Default")
      (node (ref "JP3") (pin "3") (pinfunction "3_3") (pintype "passive"))
      (node (ref "U$6") (pin "DIR") (pinfunction "DIR_DIR") (pintype "input"))
      (node (ref "U1") (pin "D5") (pinfunction "D5_D5") (pintype "bidirectional"))
    )
    (net (code "82") (name "/X-EN") (class "Default")
      (node (ref "JP3") (pin "5") (pinfunction "5_5") (pintype "passive"))
      (node (ref "R18") (pin "2") (pinfunction "2_2") (pintype "passive"))
      (node (ref "U$6") (pin "EN") (pinfunction "EN_EN") (pintype "input"))
      (node (ref "U1") (pin "D3") (pinfunction "*D3_D3") (pintype "bidirectional"))
    )
    (net (code "83") (name "/X-MAX") (class "Default")
      (node (ref "JP15") (pin "3") (pinfunction "3_3") (pintype "passive"))
      (node (ref "JP8") (pin "4") (pinfunction "4_4") (pintype "passive"))
      (node (ref "U1") (pin "D17") (pinfunction "D17_D17") (pintype "bidirectional"))
    )
    (net (code "84") (name "/X-MIN") (class "Default")
      (node (ref "JP15") (pin "1") (pinfunction "1_1") (pintype "passive"))
      (node (ref "JP8") (pin "3") (pinfunction "3_3") (pintype "passive"))
      (node (ref "U1") (pin "D16") (pinfunction "D16_D16") (pintype "bidirectional"))
    )
    (net (code "85") (name "/X-STEP") (class "Default")
      (node (ref "JP3") (pin "4") (pinfunction "4_4") (pintype "passive"))
      (node (ref "U$6") (pin "STEP") (pinfunction "STEP_STEP") (pintype "input"))
      (node (ref "U1") (pin "D4") (pinfunction "D4_D4") (pintype "bidirectional"))
    )
    (net (code "86") (name "/Y-DIR") (class "Default")
      (node (ref "JP1") (pin "8") (pinfunction "8_8") (pintype "passive"))
      (node (ref "U$7") (pin "DIR") (pinfunction "DIR_DIR") (pintype "input"))
      (node (ref "U1") (pin "D8") (pinfunction "D8_D8") (pintype "bidirectional"))
    )
    (net (code "87") (name "/Y-EN") (class "Default")
      (node (ref "JP3") (pin "2") (pinfunction "2_2") (pintype "passive"))
      (node (ref "R19") (pin "2") (pinfunction "2_2") (pintype "passive"))
      (node (ref "U$7") (pin "EN") (pinfunction "EN_EN") (pintype "input"))
      (node (ref "U1") (pin "D6") (pinfunction "D6_D6") (pintype "bidirectional"))
    )
    (net (code "88") (name "/Y-MAX") (class "Default")
      (node (ref "JP15") (pin "4") (pinfunction "4_4") (pintype "passive"))
      (node (ref "JP8") (pin "2") (pinfunction "2_2") (pintype "passive"))
      (node (ref "U1") (pin "D15") (pinfunction "D15_D15") (pintype "bidirectional"))
    )
    (net (code "89") (name "/Y-MIN") (class "Default")
      (node (ref "JP15") (pin "2") (pinfunction "2_2") (pintype "passive"))
      (node (ref "JP8") (pin "1") (pinfunction "1_1") (pintype "passive"))
      (node (ref "U1") (pin "D14") (pinfunction "D14_D14") (pintype "bidirectional"))
    )
    (net (code "90") (name "/Y-STEP") (class "Default")
      (node (ref "JP3") (pin "1") (pinfunction "1_1") (pintype "passive"))
      (node (ref "U$7") (pin "STEP") (pinfunction "STEP_STEP") (pintype "input"))
      (node (ref "U1") (pin "D7") (pinfunction "D7_D7") (pintype "bidirectional"))
    )
    (net (code "91") (name "/Z-DIR") (class "Default")
      (node (ref "CN2") (pin "2") (pinfunction "2_2") (pintype "bidirectional"))
      (node (ref "U$1") (pin "DIR") (pinfunction "DIR_DIR") (pintype "input"))
      (node (ref "U1") (pin "D32") (pinfunction "D32_D32") (pintype "bidirectional"))
    )
    (net (code "92") (name "/Z-EN") (class "Default")
      (node (ref "CN2") (pin "1") (pinfunction "1_1") (pintype "bidirectional"))
      (node (ref "R2") (pin "2") (pinfunction "2_2") (pintype "passive"))
      (node (ref "U$1") (pin "EN") (pinfunction "EN_EN") (pintype "input"))
      (node (ref "U1") (pin "D30") (pinfunction "D30_D30") (pintype "bidirectional"))
    )
    (net (code "93") (name "/Z-STEP") (class "Default")
      (node (ref "CN1") (pin "4") (pinfunction "4_4") (pintype "bidirectional"))
      (node (ref "U$1") (pin "STEP") (pinfunction "STEP_STEP") (pintype "input"))
      (node (ref "U1") (pin "D31") (pinfunction "D31_D31") (pintype "bidirectional"))
    )
    (net (code "94") (name "GND") (class "Default")
      (node (ref "C1") (pin "-") (pinfunction "-_-") (pintype "passive"))
      (node (ref "C2") (pin "2") (pinfunction "2_2") (pintype "passive"))
      (node (ref "C3") (pin "-") (pinfunction "-_-") (pintype "passive"))
      (node (ref "C4") (pin "-") (pinfunction "-_-") (pintype "passive"))
      (node (ref "C6") (pin "-") (pinfunction "-_-") (pintype "passive"))
      (node (ref "D13") (pin "C") (pinfunction "C_C") (pintype "passive"))
      (node (ref "J1") (pin "2") (pinfunction "2_2") (pintype "passive"))
      (node (ref "JP1") (pin "2") (pinfunction "2_2") (pintype "passive"))
      (node (ref "JP11") (pin "4") (pinfunction "4_4") (pintype "passive"))
      (node (ref "JP11") (pin "5") (pinfunction "5_5") (pintype "passive"))
      (node (ref "JP15") (pin "6") (pinfunction "6_6") (pintype "passive"))
      (node (ref "POWER") (pin "C") (pinfunction "C_C") (pintype "passive"))
      (node (ref "R1") (pin "2") (pinfunction "2_2") (pintype "passive"))
      (node (ref "R5") (pin "2") (pinfunction "2_2") (pintype "passive"))
      (node (ref "R8") (pin "2") (pinfunction "2_2") (pintype "passive"))
      (node (ref "RN5") (pin "6") (pinfunction "2_6") (pintype "passive"))
      (node (ref "RN5") (pin "7") (pinfunction "2_7") (pintype "passive"))
      (node (ref "RN5") (pin "8") (pinfunction "2_8") (pintype "passive"))
      (node (ref "S2") (pin "1") (pinfunction "1_1") (pintype "passive"))
      (node (ref "S2") (pin "2") (pinfunction "2_2") (pintype "passive"))
      (node (ref "SER1") (pin "1") (pinfunction "1_1") (pintype "passive"))
      (node (ref "SER2") (pin "1") (pinfunction "1_1") (pintype "passive"))
      (node (ref "TFT") (pin "1") (pinfunction "1_1") (pintype "passive"))
      (node (ref "U$1") (pin "GND") (pinfunction "GND_GND") (pintype "power_in"))
      (node (ref "U$1") (pin "GND@0") (pinfunction "GND_GND@0") (pintype "power_in"))
      (node (ref "U$6") (pin "GND") (pinfunction "GND_GND") (pintype "power_in"))
      (node (ref "U$6") (pin "GND@0") (pinfunction "GND_GND@0") (pintype "power_in"))
      (node (ref "U$7") (pin "GND") (pinfunction "GND_GND") (pintype "power_in"))
      (node (ref "U$7") (pin "GND@0") (pinfunction "GND_GND@0") (pintype "power_in"))
      (node (ref "U1") (pin "GND@0") (pinfunction "GND_GND@0") (pintype "power_in"))
      (node (ref "U1") (pin "GND@1") (pinfunction "GND_GND@1") (pintype "power_in"))
      (node (ref "U1") (pin "GND@2") (pinfunction "GND_GND@2") (pintype "power_in"))
      (node (ref "U1") (pin "GND@3") (pinfunction "GND_GND@3") (pintype "power_in"))
      (node (ref "U1") (pin "GND@4") (pinfunction "GND_GND@4") (pintype "power_in"))
      (node (ref "X1") (pin "RING") (pinfunction "RING_RING") (pintype "bidirectional"))
      (node (ref "X1") (pin "RING_SW") (pinfunction "RING_SW_RING_SW") (pintype "bidirectional"))
    )
    (net (code "95") (name "Net-(JP2-Pad1)") (class "Default")
      (node (ref "JP2") (pin "1") (pinfunction "1_1") (pintype "passive"))
      (node (ref "U$6") (pin "2B") (pinfunction "2B_2B") (pintype "output"))
      (node (ref "X-MOT") (pin "1") (pinfunction "1_1") (pintype "bidirectional"))
    )
    (net (code "96") (name "Net-(JP2-Pad2)") (class "Default")
      (node (ref "JP2") (pin "2") (pinfunction "2_2") (pintype "passive"))
      (node (ref "U$6") (pin "2A") (pinfunction "2A_2A") (pintype "output"))
      (node (ref "X-MOT") (pin "2") (pinfunction "2_2") (pintype "bidirectional"))
    )
    (net (code "97") (name "Net-(JP2-Pad3)") (class "Default")
      (node (ref "JP2") (pin "3") (pinfunction "3_3") (pintype "passive"))
      (node (ref "U$6") (pin "1A") (pinfunction "1A_1A") (pintype "output"))
      (node (ref "X-MOT") (pin "3") (pinfunction "3_3") (pintype "bidirectional"))
    )
    (net (code "98") (name "Net-(JP2-Pad4)") (class "Default")
      (node (ref "JP2") (pin "4") (pinfunction "4_4") (pintype "passive"))
      (node (ref "U$6") (pin "1B") (pinfunction "1B_1B") (pintype "output"))
      (node (ref "X-MOT") (pin "4") (pinfunction "4_4") (pintype "bidirectional"))
    )
    (net (code "99") (name "Net-(JP5-Pad1)") (class "Default")
      (node (ref "JP5") (pin "1") (pinfunction "1_1") (pintype "passive"))
      (node (ref "U$1") (pin "2B") (pinfunction "2B_2B") (pintype "output"))
      (node (ref "Z-MOT1") (pin "1") (pinfunction "1_1") (pintype "bidirectional"))
    )
    (net (code "100") (name "Net-(JP5-Pad2)") (class "Default")
      (node (ref "JP5") (pin "2") (pinfunction "2_2") (pintype "passive"))
      (node (ref "U$1") (pin "2A") (pinfunction "2A_2A") (pintype "output"))
      (node (ref "Z-MOT1") (pin "2") (pinfunction "2_2") (pintype "bidirectional"))
    )
    (net (code "101") (name "Net-(JP5-Pad3)") (class "Default")
      (node (ref "JP5") (pin "3") (pinfunction "3_3") (pintype "passive"))
      (node (ref "U$1") (pin "1A") (pinfunction "1A_1A") (pintype "output"))
      (node (ref "Z-MOT1") (pin "3") (pinfunction "3_3") (pintype "bidirectional"))
    )
    (net (code "102") (name "Net-(JP5-Pad4)") (class "Default")
      (node (ref "JP5") (pin "4") (pinfunction "4_4") (pintype "passive"))
      (node (ref "U$1") (pin "1B") (pinfunction "1B_1B") (pintype "output"))
      (node (ref "Z-MOT1") (pin "4") (pinfunction "4_4") (pintype "bidirectional"))
    )
    (net (code "103") (name "Net-(JP7-Pad1)") (class "Default")
      (node (ref "JP7") (pin "1") (pinfunction "1_1") (pintype "passive"))
      (node (ref "U$7") (pin "2B") (pinfunction "2B_2B") (pintype "output"))
      (node (ref "Y-MOT") (pin "1") (pinfunction "1_1") (pintype "bidirectional"))
    )
    (net (code "104") (name "Net-(JP7-Pad2)") (class "Default")
      (node (ref "JP7") (pin "2") (pinfunction "2_2") (pintype "passive"))
      (node (ref "U$7") (pin "2A") (pinfunction "2A_2A") (pintype "output"))
      (node (ref "Y-MOT") (pin "2") (pinfunction "2_2") (pintype "bidirectional"))
    )
    (net (code "105") (name "Net-(JP7-Pad3)") (class "Default")
      (node (ref "JP7") (pin "3") (pinfunction "3_3") (pintype "passive"))
      (node (ref "U$7") (pin "1A") (pinfunction "1A_1A") (pintype "output"))
      (node (ref "Y-MOT") (pin "3") (pinfunction "3_3") (pintype "bidirectional"))
    )
    (net (code "106") (name "Net-(JP7-Pad4)") (class "Default")
      (node (ref "JP7") (pin "4") (pinfunction "4_4") (pintype "passive"))
      (node (ref "U$7") (pin "1B") (pinfunction "1B_1B") (pintype "output"))
      (node (ref "Y-MOT") (pin "4") (pinfunction "4_4") (pintype "bidirectional"))
    )
    (net (code "107") (name "Net-(POWER-PadA)") (class "Default")
      (node (ref "POWER") (pin "A") (pinfunction "A_A") (pintype "passive"))
      (node (ref "R41") (pin "1") (pinfunction "1_1") (pintype "passive"))
    )
    (net (code "108") (name "Net-(R1-Pad1)") (class "Default")
      (node (ref "R1") (pin "1") (pinfunction "1_1") (pintype "passive"))
      (node (ref "SJ7") (pin "2") (pinfunction "2_2") (pintype "passive"))
      (node (ref "U$1") (pin "MS1") (pinfunction "MS1_MS1") (pintype "input"))
    )
    (net (code "109") (name "Net-(R5-Pad1)") (class "Default")
      (node (ref "R5") (pin "1") (pinfunction "1_1") (pintype "passive"))
      (node (ref "SJ1") (pin "2") (pinfunction "2_2") (pintype "passive"))
      (node (ref "U$6") (pin "MS1") (pinfunction "MS1_MS1") (pintype "input"))
    )
    (net (code "110") (name "Net-(R8-Pad1)") (class "Default")
      (node (ref "R8") (pin "1") (pinfunction "1_1") (pintype "passive"))
      (node (ref "SJ3") (pin "2") (pinfunction "2_2") (pintype "passive"))
      (node (ref "U$7") (pin "MS1") (pinfunction "MS1_MS1") (pintype "input"))
    )
    (net (code "111") (name "Net-(SJ2-Pad2)") (class "Default")
      (node (ref "SJ2") (pin "2") (pinfunction "2_2") (pintype "passive"))
      (node (ref "U$6") (pin "MS2") (pinfunction "MS2_MS2") (pintype "input"))
    )
    (net (code "112") (name "Net-(SJ4-Pad2)") (class "Default")
      (node (ref "SJ4") (pin "2") (pinfunction "2_2") (pintype "passive"))
      (node (ref "U$7") (pin "MS2") (pinfunction "MS2_MS2") (pintype "input"))
    )
    (net (code "113") (name "Net-(SJ5-Pad2)") (class "Default")
      (node (ref "SJ5") (pin "2") (pinfunction "2_2") (pintype "passive"))
      (node (ref "U$6") (pin "MS3") (pinfunction "MS3_MS3") (pintype "input"))
    )
    (net (code "114") (name "Net-(SJ6-Pad2)") (class "Default")
      (node (ref "SJ6") (pin "2") (pinfunction "2_2") (pintype "passive"))
      (node (ref "U$7") (pin "MS3") (pinfunction "MS3_MS3") (pintype "input"))
    )
    (net (code "115") (name "Net-(SJ8-Pad2)") (class "Default")
      (node (ref "SJ8") (pin "2") (pinfunction "2_2") (pintype "passive"))
      (node (ref "U$1") (pin "MS2") (pinfunction "MS2_MS2") (pintype "input"))
    )
    (net (code "116") (name "Net-(SJ9-Pad2)") (class "Default")
      (node (ref "SJ9") (pin "2") (pinfunction "2_2") (pintype "passive"))
      (node (ref "U$1") (pin "MS3") (pinfunction "MS3_MS3") (pintype "input"))
    )
    (net (code "117") (name "Net-(U$1-SLEEP)") (class "Default")
      (node (ref "U$1") (pin "RST") (pinfunction "RST_RST") (pintype "input"))
      (node (ref "U$1") (pin "SLP") (pinfunction "SLEEP_SLP") (pintype "input"))
    )
    (net (code "118") (name "Net-(U$6-SLEEP)") (class "Default")
      (node (ref "U$6") (pin "RST") (pinfunction "RST_RST") (pintype "input"))
      (node (ref "U$6") (pin "SLP") (pinfunction "SLEEP_SLP") (pintype "input"))
    )
    (net (code "119") (name "Net-(U$7-SLEEP)") (class "Default")
      (node (ref "U$7") (pin "RST") (pinfunction "RST_RST") (pintype "input"))
      (node (ref "U$7") (pin "SLP") (pinfunction "SLEEP_SLP") (pintype "input"))
    )
    (net (code "120") (name "VCC") (class "Default")
      (node (ref "JP11") (pin "3") (pinfunction "3_3") (pintype "passive"))
      (node (ref "JP15") (pin "5") (pinfunction "5_5") (pintype "passive"))
      (node (ref "R18") (pin "1") (pinfunction "1_1") (pintype "passive"))
      (node (ref "R19") (pin "1") (pinfunction "1_1") (pintype "passive"))
      (node (ref "R2") (pin "1") (pinfunction "1_1") (pintype "passive"))
      (node (ref "R41") (pin "2") (pinfunction "2_2") (pintype "passive"))
      (node (ref "SER1") (pin "2") (pinfunction "2_2") (pintype "passive"))
      (node (ref "SER2") (pin "2") (pinfunction "2_2") (pintype "passive"))
      (node (ref "SJ1") (pin "1") (pinfunction "1_1") (pintype "passive"))
      (node (ref "SJ2") (pin "1") (pinfunction "1_1") (pintype "passive"))
      (node (ref "SJ3") (pin "1") (pinfunction "1_1") (pintype "passive"))
      (node (ref "SJ4") (pin "1") (pinfunction "1_1") (pintype "passive"))
      (node (ref "SJ5") (pin "1") (pinfunction "1_1") (pintype "passive"))
      (node (ref "SJ6") (pin "1") (pinfunction "1_1") (pintype "passive"))
      (node (ref "SJ7") (pin "1") (pinfunction "1_1") (pintype "passive"))
      (node (ref "SJ8") (pin "1") (pinfunction "1_1") (pintype "passive"))
      (node (ref "SJ9") (pin "1") (pinfunction "1_1") (pintype "passive"))
      (node (ref "TFT") (pin "3") (pinfunction "3_3") (pintype "passive"))
      (node (ref "U$1") (pin "VDD") (pinfunction "VDD_VDD") (pintype "power_in"))
      (node (ref "U$6") (pin "VDD") (pinfunction "VDD_VDD") (pintype "power_in"))
      (node (ref "U$7") (pin "VDD") (pinfunction "VDD_VDD") (pintype "power_in"))
      (node (ref "U1") (pin "5V@0") (pinfunction "5V_5V@0") (pintype "power_in"))
      (node (ref "U1") (pin "5V@1") (pinfunction "5V_5V@1") (pintype "power_in"))
      (node (ref "U1") (pin "5V@2") (pinfunction "5V_5V@2") (pintype "power_in"))
    )
    (net (code "121") (name "unconnected-(TFT-Pad2)") (class "Default")
      (node (ref "TFT") (pin "2") (pinfunction "2_2") (pintype "passive"))
    )
    (net (code "122") (name "unconnected-(TFT-Pad4)") (class "Default")
      (node (ref "TFT") (pin "4") (pinfunction "4_4") (pintype "passive"))
    )
    (net (code "123") (name "unconnected-(TFT-Pad5)") (class "Default")
      (node (ref "TFT") (pin "5") (pinfunction "5_5") (pintype "passive"))
    )
    (net (code "124") (name "unconnected-(TFT-Pad6)") (class "Default")
      (node (ref "TFT") (pin "6") (pinfunction "6_6") (pintype "passive"))
    )
    (net (code "125") (name "unconnected-(TFT-Pad8)") (class "Default")
      (node (ref "TFT") (pin "8") (pinfunction "8_8") (pintype "passive"))
    )
    (net (code "126") (name "unconnected-(TFT-Pad10)") (class "Default")
      (node (ref "TFT") (pin "10") (pinfunction "10_10") (pintype "passive"))
    )
    (net (code "127") (name "unconnected-(TFT-Pad12)") (class "Default")
      (node (ref "TFT") (pin "12") (pinfunction "12_12") (pintype "passive"))
    )
    (net (code "128") (name "unconnected-(TFT-Pad14)") (class "Default")
      (node (ref "TFT") (pin "14") (pinfunction "14_14") (pintype "passive"))
    )
    (net (code "129") (name "unconnected-(TFT-Pad16)") (class "Default")
      (node (ref "TFT") (pin "16") (pinfunction "16_16") (pintype "passive"))
    )
    (net (code "130") (name "unconnected-(TFT-Pad24)") (class "Default")
      (node (ref "TFT") (pin "24") (pinfunction "24_24") (pintype "passive"))
    )
    (net (code "131") (name "unconnected-(TFT-Pad31)") (class "Default")
      (node (ref "TFT") (pin "31") (pinfunction "31_31") (pintype "passive"))
    )
    (net (code "132") (name "unconnected-(TFT-Pad35)") (class "Default")
      (node (ref "TFT") (pin "35") (pinfunction "35_35") (pintype "passive"))
    )
    (net (code "133") (name "unconnected-(TFT-Pad38)") (class "Default")
      (node (ref "TFT") (pin "38") (pinfunction "38_38") (pintype "passive"))
    )
    (net (code "134") (name "unconnected-(TFT-Pad39)") (class "Default")
      (node (ref "TFT") (pin "39") (pinfunction "39_39") (pintype "passive"))
    )
    (net (code "135") (name "unconnected-(TFT-Pad40)") (class "Default")
      (node (ref "TFT") (pin "40") (pinfunction "40_40") (pintype "passive"))
    )
  )
)
